# REED_wy_v1_0.net
KiCad netlist of a schematic drawn in Altium Designer
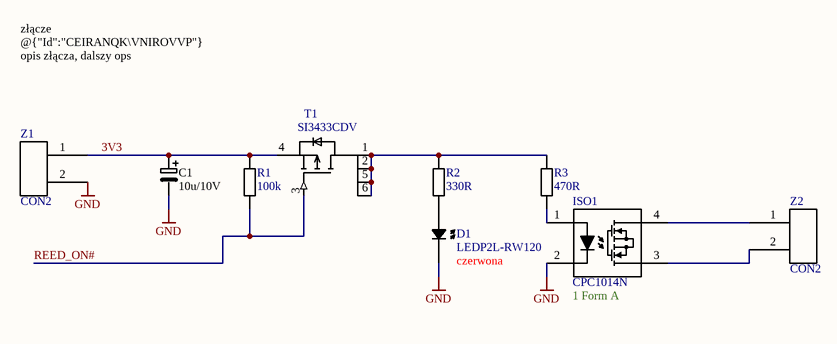
[diagram p0: REED_wy_v1_0.SchDoc]

(export (version "E")
  (design (tool "Eeschema 10.0.6"))
  (components
    (comp (ref "C1")
      (value "10u/10V")
      (footprint "R1206-mod")
      (description "Kondensator elektrolityczny")
      (libsource (lib "*") (part "CP"))
    )
    (comp (ref "D1")
      (value "LEDP2L-RW120")
      (footprint "R1206-mod")
      (description "LED")
      (fields (field (name "UWAGI") "czerwona") (field (name "AUTOR") "Matysiuk Dariusz"))
      (libsource (lib "Ok_Library") (part "LED"))
    )
    (comp (ref "ISO1")
      (value "CPC1014N")
      (footprint "SOP-4")
      (description "Solid State Relay; 1 Form A, 60V; 400mA.")
      (fields (field (name "FUNCTION") "1 Form A"))
      (libsource (lib "M4E") (part "CPC1014N"))
    )
    (comp (ref "R1")
      (value "100k")
      (footprint "R1206-mod")
      (description "Rezystor")
      (libsource (lib "Ok_Library") (part "R"))
    )
    (comp (ref "R2")
      (value "330R")
      (footprint "R1206-mod")
      (description "Rezystor")
      (libsource (lib "Ok_Library") (part "R"))
    )
    (comp (ref "R3")
      (value "470R")
      (footprint "R1206-mod")
      (description "Rezystor")
      (libsource (lib "Ok_Library") (part "R"))
    )
    (comp (ref "T1")
      (value "SI3433CDV")
      (footprint "MacR6:TSOP6_3d")
      (description "p-MOSFET")
      (libsource (lib "*") (part "SI3441DV"))
    )
    (comp (ref "Z1") (value "CON2") (footprint "CAPC1005X05N") (libsource (lib "Comb_lib1") (part "CON2")))
    (comp (ref "Z2") (value "CON2") (footprint "CAPC1005X05N") (libsource (lib "") (part "CON2_1")))
  )
  (nets
    (net (code "1") (name "/3V3") (class "Default")
      (node (ref "C1") (pin "1") (pinfunction "1_1") (pintype "passive"))
      (node (ref "R1") (pin "2") (pinfunction "2_2") (pintype "passive"))
      (node (ref "T1") (pin "4") (pinfunction "S_4") (pintype "passive"))
      (node (ref "Z1") (pin "1") (pintype "passive"))
    )
    (net (code "2") (name "/REED_ON#") (class "Default")
      (node (ref "R1") (pin "1") (pinfunction "1_1") (pintype "passive"))
      (node (ref "T1") (pin "3") (pinfunction "G_3") (pintype "input"))
    )
    (net (code "3") (name "GND") (class "Default")
      (node (ref "C1") (pin "2") (pinfunction "2_2") (pintype "passive"))
      (node (ref "D1") (pin "1") (pinfunction "1_1") (pintype "passive"))
      (node (ref "ISO1") (pin "2") (pinfunction "K_2") (pintype "passive"))
      (node (ref "Z1") (pin "2") (pintype "passive"))
    )
    (net (code "4") (name "Net-(D1-Pad2)") (class "Default")
      (node (ref "D1") (pin "2") (pinfunction "2_2") (pintype "passive"))
      (node (ref "R2") (pin "1") (pinfunction "1_1") (pintype "passive"))
    )
    (net (code "5") (name "Net-(ISO1-A)") (class "Default")
      (node (ref "ISO1") (pin "1") (pinfunction "A_1") (pintype "passive"))
      (node (ref "R3") (pin "1") (pinfunction "1_1") (pintype "passive"))
    )
    (net (code "6") (name "Net-(ISO1-S)") (class "Default")
      (node (ref "ISO1") (pin "4") (pinfunction "S_4") (pintype "passive"))
      (node (ref "Z2") (pin "1") (pintype "passive"))
    )
    (net (code "7") (name "Net-(ISO1-S1)") (class "Default")
      (node (ref "ISO1") (pin "3") (pinfunction "S1_3") (pintype "passive"))
      (node (ref "Z2") (pin "2") (pintype "passive"))
    )
    (net (code "8") (name "Net-(R2-Pad2)") (class "Default")
      (node (ref "R2") (pin "2") (pinfunction "2_2") (pintype "passive"))
      (node (ref "R3") (pin "2") (pinfunction "2_2") (pintype "passive"))
      (node (ref "T1") (pin "1") (pinfunction "D_1") (pintype "passive"))
      (node (ref "T1") (pin "2") (pinfunction "D_2") (pintype "passive"))
      (node (ref "T1") (pin "5") (pinfunction "D_5") (pintype "passive"))
      (node (ref "T1") (pin "6") (pinfunction "D_6") (pintype "passive"))
    )
  )
)
